# H3_SWPad_Small_Rev_2.net
KiCad netlist of a schematic drawn in EAGLE
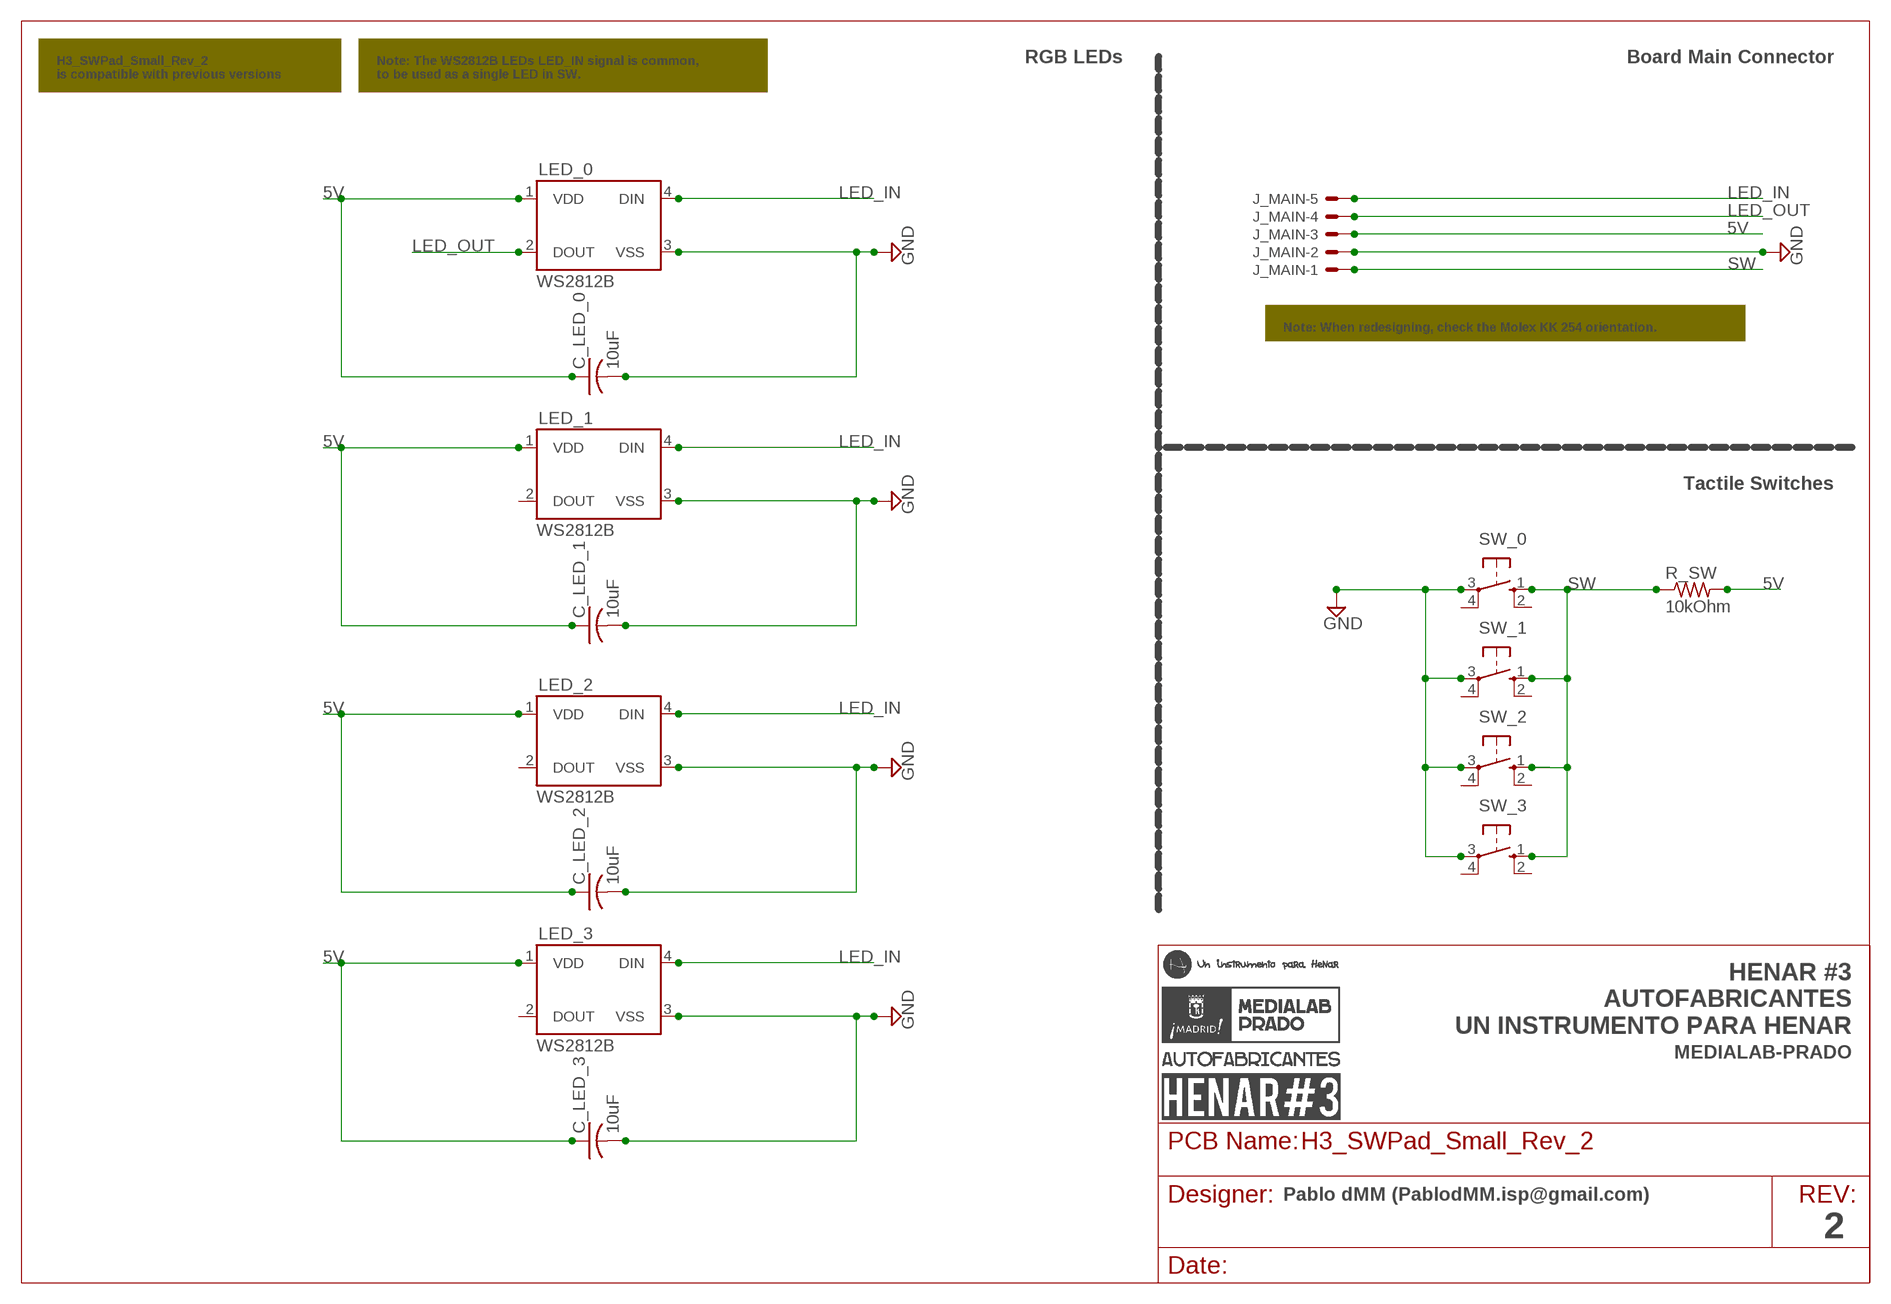
[diagram p0: schematic, sheet 1]

(export (version "E")
  (design (tool "Eeschema 10.0.6"))
  (components
    (comp (ref "C_LED_0")
      (value "10uF")
      (footprint "eagle-import:C1206K")
      (libsource (lib "eagle-import") (part "C-USC1206K"))
    )
    (comp (ref "C_LED_1")
      (value "10uF")
      (footprint "eagle-import:C1206K")
      (libsource (lib "eagle-import") (part "C-USC1206K"))
    )
    (comp (ref "C_LED_2")
      (value "10uF")
      (footprint "eagle-import:C1206K")
      (libsource (lib "eagle-import") (part "C-USC1206K"))
    )
    (comp (ref "C_LED_3")
      (value "10uF")
      (footprint "eagle-import:C1206K")
      (libsource (lib "eagle-import") (part "C-USC1206K"))
    )
    (comp (ref "J_MAIN")
      (value "22-05-7058-05")
      (footprint "eagle-import:7395-05")
      (libsource (lib "eagle-import") (part "22-?-0505-7058"))
    )
    (comp (ref "LED_0")
      (value "WS2812B")
      (footprint "eagle-import:WS2812B")
      (libsource (lib "eagle-import") (part "WS2812B"))
    )
    (comp (ref "LED_1")
      (value "WS2812B")
      (footprint "eagle-import:WS2812B")
      (libsource (lib "eagle-import") (part "WS2812B"))
    )
    (comp (ref "LED_2")
      (value "WS2812B")
      (footprint "eagle-import:WS2812B")
      (libsource (lib "eagle-import") (part "WS2812B"))
    )
    (comp (ref "LED_3")
      (value "WS2812B")
      (footprint "eagle-import:WS2812B")
      (libsource (lib "eagle-import") (part "WS2812B"))
    )
    (comp (ref "R_SW")
      (value "10kOhm")
      (footprint "eagle-import:R1206W")
      (libsource (lib "eagle-import") (part "R-US_R1206W"))
    )
    (comp (ref "SW_0")
      (value "10-XX")
      (footprint "eagle-import:B3F-10XX")
      (fields (field (name "MPN") "B3F-1000"))
      (libsource (lib "eagle-import") (part "10-XX"))
    )
    (comp (ref "SW_1")
      (value "10-XX")
      (footprint "eagle-import:B3F-10XX")
      (fields (field (name "MPN") "B3F-1000"))
      (libsource (lib "eagle-import") (part "10-XX"))
    )
    (comp (ref "SW_2")
      (value "10-XX")
      (footprint "eagle-import:B3F-10XX")
      (fields (field (name "MPN") "B3F-1000"))
      (libsource (lib "eagle-import") (part "10-XX"))
    )
    (comp (ref "SW_3")
      (value "10-XX")
      (footprint "eagle-import:B3F-10XX")
      (fields (field (name "MPN") "B3F-1000"))
      (libsource (lib "eagle-import") (part "10-XX"))
    )
  )
  (nets
    (net (code "1") (name "/5V") (class "Default")
      (node (ref "C_LED_0") (pin "1") (pinfunction "1_1") (pintype "passive"))
      (node (ref "C_LED_1") (pin "1") (pinfunction "1_1") (pintype "passive"))
      (node (ref "C_LED_2") (pin "1") (pinfunction "1_1") (pintype "passive"))
      (node (ref "C_LED_3") (pin "1") (pinfunction "1_1") (pintype "passive"))
      (node (ref "J_MAIN") (pin "3") (pinfunction "S_3") (pintype "passive"))
      (node (ref "LED_0") (pin "1") (pinfunction "VDD_1") (pintype "power_in"))
      (node (ref "LED_1") (pin "1") (pinfunction "VDD_1") (pintype "power_in"))
      (node (ref "LED_2") (pin "1") (pinfunction "VDD_1") (pintype "power_in"))
      (node (ref "LED_3") (pin "1") (pinfunction "VDD_1") (pintype "power_in"))
      (node (ref "R_SW") (pin "2") (pinfunction "2_2") (pintype "passive"))
    )
    (net (code "2") (name "/LED_IN") (class "Default")
      (node (ref "J_MAIN") (pin "5") (pinfunction "S_5") (pintype "passive"))
      (node (ref "LED_0") (pin "4") (pinfunction "DIN_4") (pintype "input"))
      (node (ref "LED_1") (pin "4") (pinfunction "DIN_4") (pintype "input"))
      (node (ref "LED_2") (pin "4") (pinfunction "DIN_4") (pintype "input"))
      (node (ref "LED_3") (pin "4") (pinfunction "DIN_4") (pintype "input"))
    )
    (net (code "3") (name "/LED_OUT") (class "Default")
      (node (ref "J_MAIN") (pin "4") (pinfunction "S_4") (pintype "passive"))
      (node (ref "LED_0") (pin "2") (pinfunction "DOUT_2") (pintype "output"))
    )
    (net (code "4") (name "/SW") (class "Default")
      (node (ref "J_MAIN") (pin "1") (pinfunction "S_1") (pintype "passive"))
      (node (ref "R_SW") (pin "1") (pinfunction "1_1") (pintype "passive"))
      (node (ref "SW_0") (pin "1") (pinfunction "S_1") (pintype "passive"))
      (node (ref "SW_1") (pin "1") (pinfunction "S_1") (pintype "passive"))
      (node (ref "SW_2") (pin "1") (pinfunction "S_1") (pintype "passive"))
      (node (ref "SW_3") (pin "1") (pinfunction "S_1") (pintype "passive"))
    )
    (net (code "5") (name "GND") (class "Default")
      (node (ref "C_LED_0") (pin "2") (pinfunction "2_2") (pintype "passive"))
      (node (ref "C_LED_1") (pin "2") (pinfunction "2_2") (pintype "passive"))
      (node (ref "C_LED_2") (pin "2") (pinfunction "2_2") (pintype "passive"))
      (node (ref "C_LED_3") (pin "2") (pinfunction "2_2") (pintype "passive"))
      (node (ref "J_MAIN") (pin "2") (pinfunction "S_2") (pintype "passive"))
      (node (ref "LED_0") (pin "3") (pinfunction "VSS_3") (pintype "power_in"))
      (node (ref "LED_1") (pin "3") (pinfunction "VSS_3") (pintype "power_in"))
      (node (ref "LED_2") (pin "3") (pinfunction "VSS_3") (pintype "power_in"))
      (node (ref "LED_3") (pin "3") (pinfunction "VSS_3") (pintype "power_in"))
      (node (ref "SW_0") (pin "3") (pinfunction "P_3") (pintype "passive"))
      (node (ref "SW_1") (pin "3") (pinfunction "P_3") (pintype "passive"))
      (node (ref "SW_2") (pin "3") (pinfunction "P_3") (pintype "passive"))
      (node (ref "SW_3") (pin "3") (pinfunction "P_3") (pintype "passive"))
    )
    (net (code "6") (name "unconnected-(LED_1-DOUT-Pad2)") (class "Default")
      (node (ref "LED_1") (pin "2") (pinfunction "DOUT_2") (pintype "output"))
    )
    (net (code "7") (name "unconnected-(LED_2-DOUT-Pad2)") (class "Default")
      (node (ref "LED_2") (pin "2") (pinfunction "DOUT_2") (pintype "output"))
    )
    (net (code "8") (name "unconnected-(LED_3-DOUT-Pad2)") (class "Default")
      (node (ref "LED_3") (pin "2") (pinfunction "DOUT_2") (pintype "output"))
    )
    (net (code "9") (name "unconnected-(SW_0-P1-Pad4)") (class "Default")
      (node (ref "SW_0") (pin "4") (pinfunction "P1_4") (pintype "passive"))
    )
    (net (code "10") (name "unconnected-(SW_0-S1-Pad2)") (class "Default")
      (node (ref "SW_0") (pin "2") (pinfunction "S1_2") (pintype "passive"))
    )
    (net (code "11") (name "unconnected-(SW_1-P1-Pad4)") (class "Default")
      (node (ref "SW_1") (pin "4") (pinfunction "P1_4") (pintype "passive"))
    )
    (net (code "12") (name "unconnected-(SW_1-S1-Pad2)") (class "Default")
      (node (ref "SW_1") (pin "2") (pinfunction "S1_2") (pintype "passive"))
    )
    (net (code "13") (name "unconnected-(SW_2-P1-Pad4)") (class "Default")
      (node (ref "SW_2") (pin "4") (pinfunction "P1_4") (pintype "passive"))
    )
    (net (code "14") (name "unconnected-(SW_2-S1-Pad2)") (class "Default")
      (node (ref "SW_2") (pin "2") (pinfunction "S1_2") (pintype "passive"))
    )
    (net (code "15") (name "unconnected-(SW_3-P1-Pad4)") (class "Default")
      (node (ref "SW_3") (pin "4") (pinfunction "P1_4") (pintype "passive"))
    )
    (net (code "16") (name "unconnected-(SW_3-S1-Pad2)") (class "Default")
      (node (ref "SW_3") (pin "2") (pinfunction "S1_2") (pintype "passive"))
    )
  )
)
